# frame_LNA.net
KiCad netlist of a schematic drawn in EAGLE
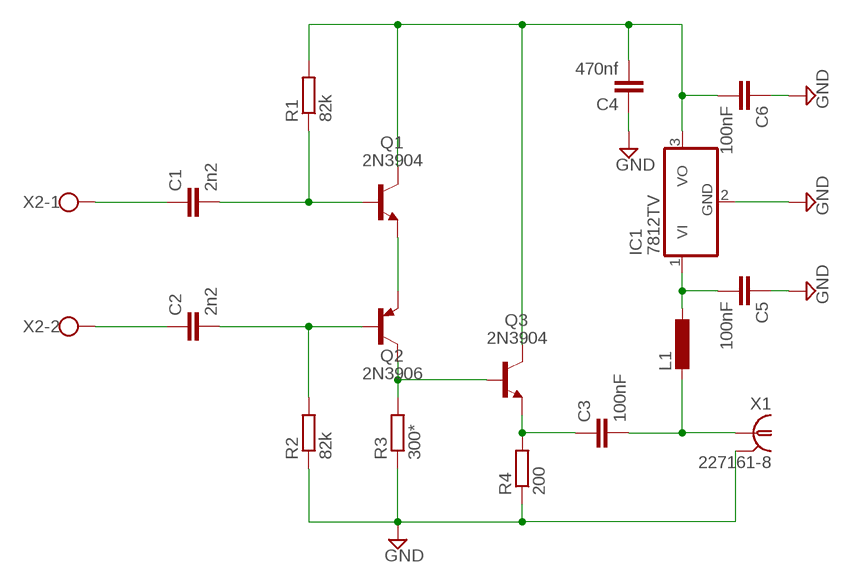
[diagram p0: schematic, sheet 1]

(export (version "E")
  (design (tool "Eeschema 10.0.6"))
  (components
    (comp (ref "C1")
      (value "2n2")
      (footprint "eagle-import:C0805K")
      (libsource (lib "eagle-import") (part "C-EUC0805K"))
    )
    (comp (ref "C2")
      (value "2n2")
      (footprint "eagle-import:C0805K")
      (libsource (lib "eagle-import") (part "C-EUC0805K"))
    )
    (comp (ref "C3")
      (value "100nF")
      (footprint "eagle-import:C0805K")
      (libsource (lib "eagle-import") (part "C-EUC0805K"))
    )
    (comp (ref "C4")
      (value "470nf")
      (footprint "eagle-import:C0805K")
      (libsource (lib "eagle-import") (part "C-EUC0805K"))
    )
    (comp (ref "C5")
      (value "100nF")
      (footprint "eagle-import:C0805K")
      (libsource (lib "eagle-import") (part "C-EUC0805K"))
    )
    (comp (ref "C6")
      (value "100nF")
      (footprint "eagle-import:C0805K")
      (libsource (lib "eagle-import") (part "C-EUC0805K"))
    )
    (comp (ref "IC1")
      (value "7812TV")
      (footprint "eagle-import:TO220V")
      (libsource (lib "eagle-import") (part "78TV12"))
    )
    (comp (ref "L1")
      (value "L-EU0207/12")
      (footprint "eagle-import:0207_12")
      (libsource (lib "eagle-import") (part "L-EU0207/12"))
    )
    (comp (ref "Q1")
      (value "2N3904")
      (footprint "eagle-import:TO92")
      (libsource (lib "eagle-import") (part "2N3904"))
    )
    (comp (ref "Q2")
      (value "2N3906")
      (footprint "eagle-import:TO92")
      (libsource (lib "eagle-import") (part "2N3906"))
    )
    (comp (ref "Q3")
      (value "2N3904")
      (footprint "eagle-import:TO92")
      (libsource (lib "eagle-import") (part "2N3904"))
    )
    (comp (ref "R1")
      (value "82k")
      (footprint "eagle-import:R0805")
      (libsource (lib "eagle-import") (part "R-EU_R0805"))
    )
    (comp (ref "R2")
      (value "82k")
      (footprint "eagle-import:R0805")
      (libsource (lib "eagle-import") (part "R-EU_R0805"))
    )
    (comp (ref "R3")
      (value "300*")
      (footprint "eagle-import:R0805")
      (libsource (lib "eagle-import") (part "R-EU_R0805"))
    )
    (comp (ref "R4")
      (value "200")
      (footprint "eagle-import:R0805")
      (libsource (lib "eagle-import") (part "R-EU_R0805"))
    )
    (comp (ref "X1")
      (value "227161-8")
      (footprint "eagle-import:AMP_227161")
      (libsource (lib "eagle-import") (part "?227161-8"))
    )
    (comp (ref "X2")
      (value "W237-102")
      (footprint "eagle-import:W237-102")
      (fields (field (name "MPN") "237-102"))
      (libsource (lib "eagle-import") (part "W237-102"))
    )
  )
  (nets
    (net (code "1") (name "GND") (class "Default")
      (node (ref "C4") (pin "1") (pinfunction "1_1") (pintype "passive"))
      (node (ref "C5") (pin "1") (pinfunction "1_1") (pintype "passive"))
      (node (ref "C6") (pin "1") (pinfunction "1_1") (pintype "passive"))
      (node (ref "IC1") (pin "2") (pinfunction "GND_2") (pintype "passive"))
      (node (ref "R2") (pin "1") (pinfunction "1_1") (pintype "passive"))
      (node (ref "R3") (pin "1") (pinfunction "1_1") (pintype "passive"))
      (node (ref "R4") (pin "1") (pinfunction "1_1") (pintype "passive"))
      (node (ref "X1") (pin "2") (pinfunction "2_2") (pintype "passive"))
    )
    (net (code "2") (name "Net-(C3-Pad2)") (class "Default")
      (node (ref "C3") (pin "2") (pinfunction "2_2") (pintype "passive"))
      (node (ref "L1") (pin "2") (pinfunction "2_2") (pintype "passive"))
      (node (ref "X1") (pin "1") (pinfunction "1_1") (pintype "passive"))
    )
    (net (code "3") (name "Net-(IC1-VI)") (class "Default")
      (node (ref "C5") (pin "2") (pinfunction "2_2") (pintype "passive"))
      (node (ref "IC1") (pin "1") (pinfunction "VI_1") (pintype "input"))
      (node (ref "L1") (pin "1") (pinfunction "1_1") (pintype "passive"))
    )
    (net (code "4") (name "Net-(IC1-VO)") (class "Default")
      (node (ref "C4") (pin "2") (pinfunction "2_2") (pintype "passive"))
      (node (ref "C6") (pin "2") (pinfunction "2_2") (pintype "passive"))
      (node (ref "IC1") (pin "3") (pinfunction "VO_3") (pintype "passive"))
      (node (ref "Q1") (pin "1") (pinfunction "C_1") (pintype "passive"))
      (node (ref "Q3") (pin "1") (pinfunction "C_1") (pintype "passive"))
      (node (ref "R1") (pin "2") (pinfunction "2_2") (pintype "passive"))
    )
    (net (code "5") (name "Net-(Q1-B)") (class "Default")
      (node (ref "C1") (pin "2") (pinfunction "2_2") (pintype "passive"))
      (node (ref "Q1") (pin "2") (pinfunction "B_2") (pintype "passive"))
      (node (ref "R1") (pin "1") (pinfunction "1_1") (pintype "passive"))
    )
    (net (code "6") (name "Net-(Q1-E)") (class "Default")
      (node (ref "Q1") (pin "3") (pinfunction "E_3") (pintype "passive"))
      (node (ref "Q2") (pin "3") (pinfunction "E_3") (pintype "passive"))
    )
    (net (code "7") (name "Net-(Q2-B)") (class "Default")
      (node (ref "C2") (pin "2") (pinfunction "2_2") (pintype "passive"))
      (node (ref "Q2") (pin "2") (pinfunction "B_2") (pintype "passive"))
      (node (ref "R2") (pin "2") (pinfunction "2_2") (pintype "passive"))
    )
    (net (code "8") (name "Net-(Q2-C)") (class "Default")
      (node (ref "Q2") (pin "1") (pinfunction "C_1") (pintype "passive"))
      (node (ref "Q3") (pin "2") (pinfunction "B_2") (pintype "passive"))
      (node (ref "R3") (pin "2") (pinfunction "2_2") (pintype "passive"))
    )
    (net (code "9") (name "Net-(Q3-E)") (class "Default")
      (node (ref "C3") (pin "1") (pinfunction "1_1") (pintype "passive"))
      (node (ref "Q3") (pin "3") (pinfunction "E_3") (pintype "passive"))
      (node (ref "R4") (pin "2") (pinfunction "2_2") (pintype "passive"))
    )
    (net (code "10") (name "Net-(X2A-KL)") (class "Default")
      (node (ref "C1") (pin "1") (pinfunction "1_1") (pintype "passive"))
      (node (ref "X2") (pin "1") (pinfunction "KL_1") (pintype "passive"))
    )
    (net (code "11") (name "Net-(X2B-KL)") (class "Default")
      (node (ref "C2") (pin "1") (pinfunction "1_1") (pintype "passive"))
      (node (ref "X2") (pin "2") (pinfunction "KL_2") (pintype "passive"))
    )
  )
)
